# relay.net
KiCad netlist of a schematic drawn in Altium Designer
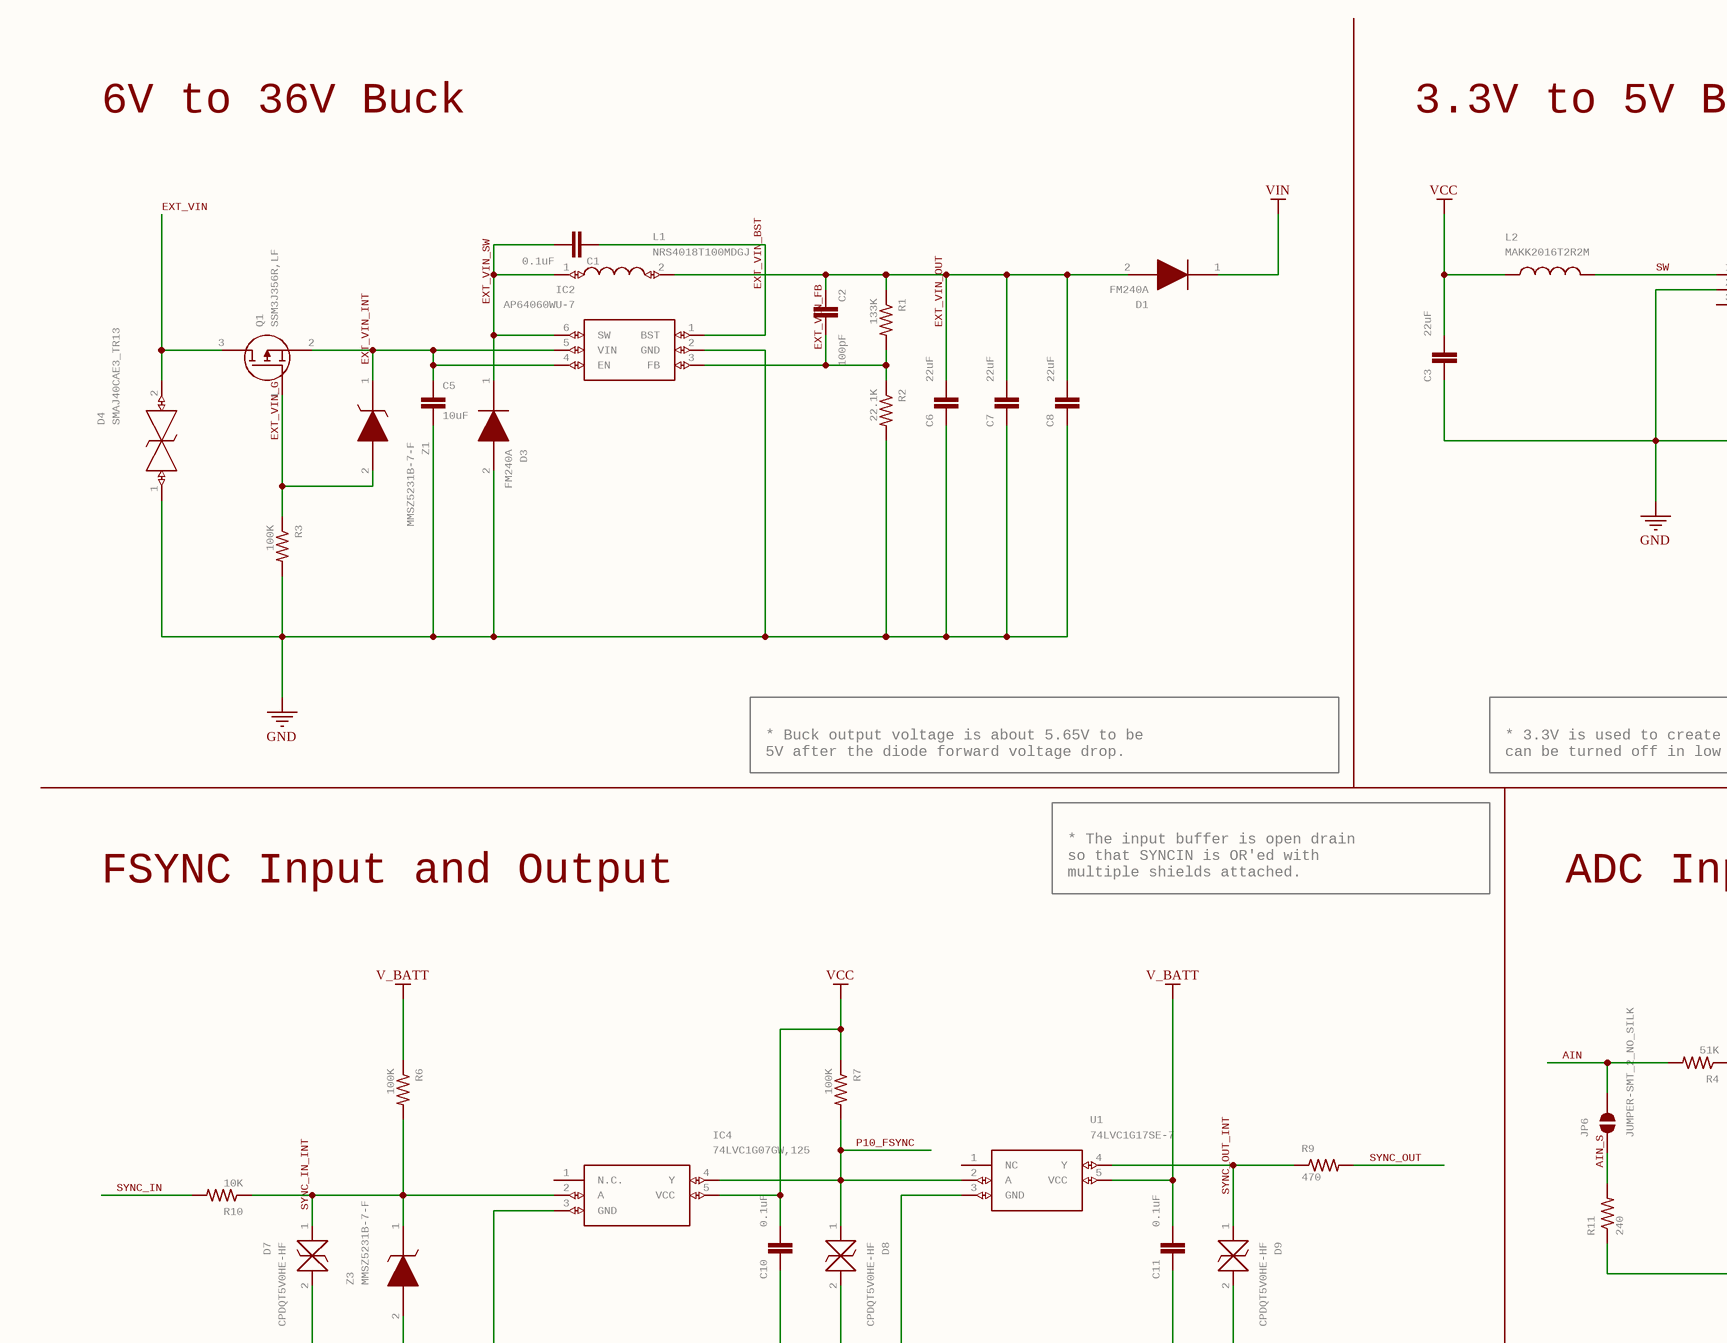
[diagram p0: relay.SchDoc, top left]
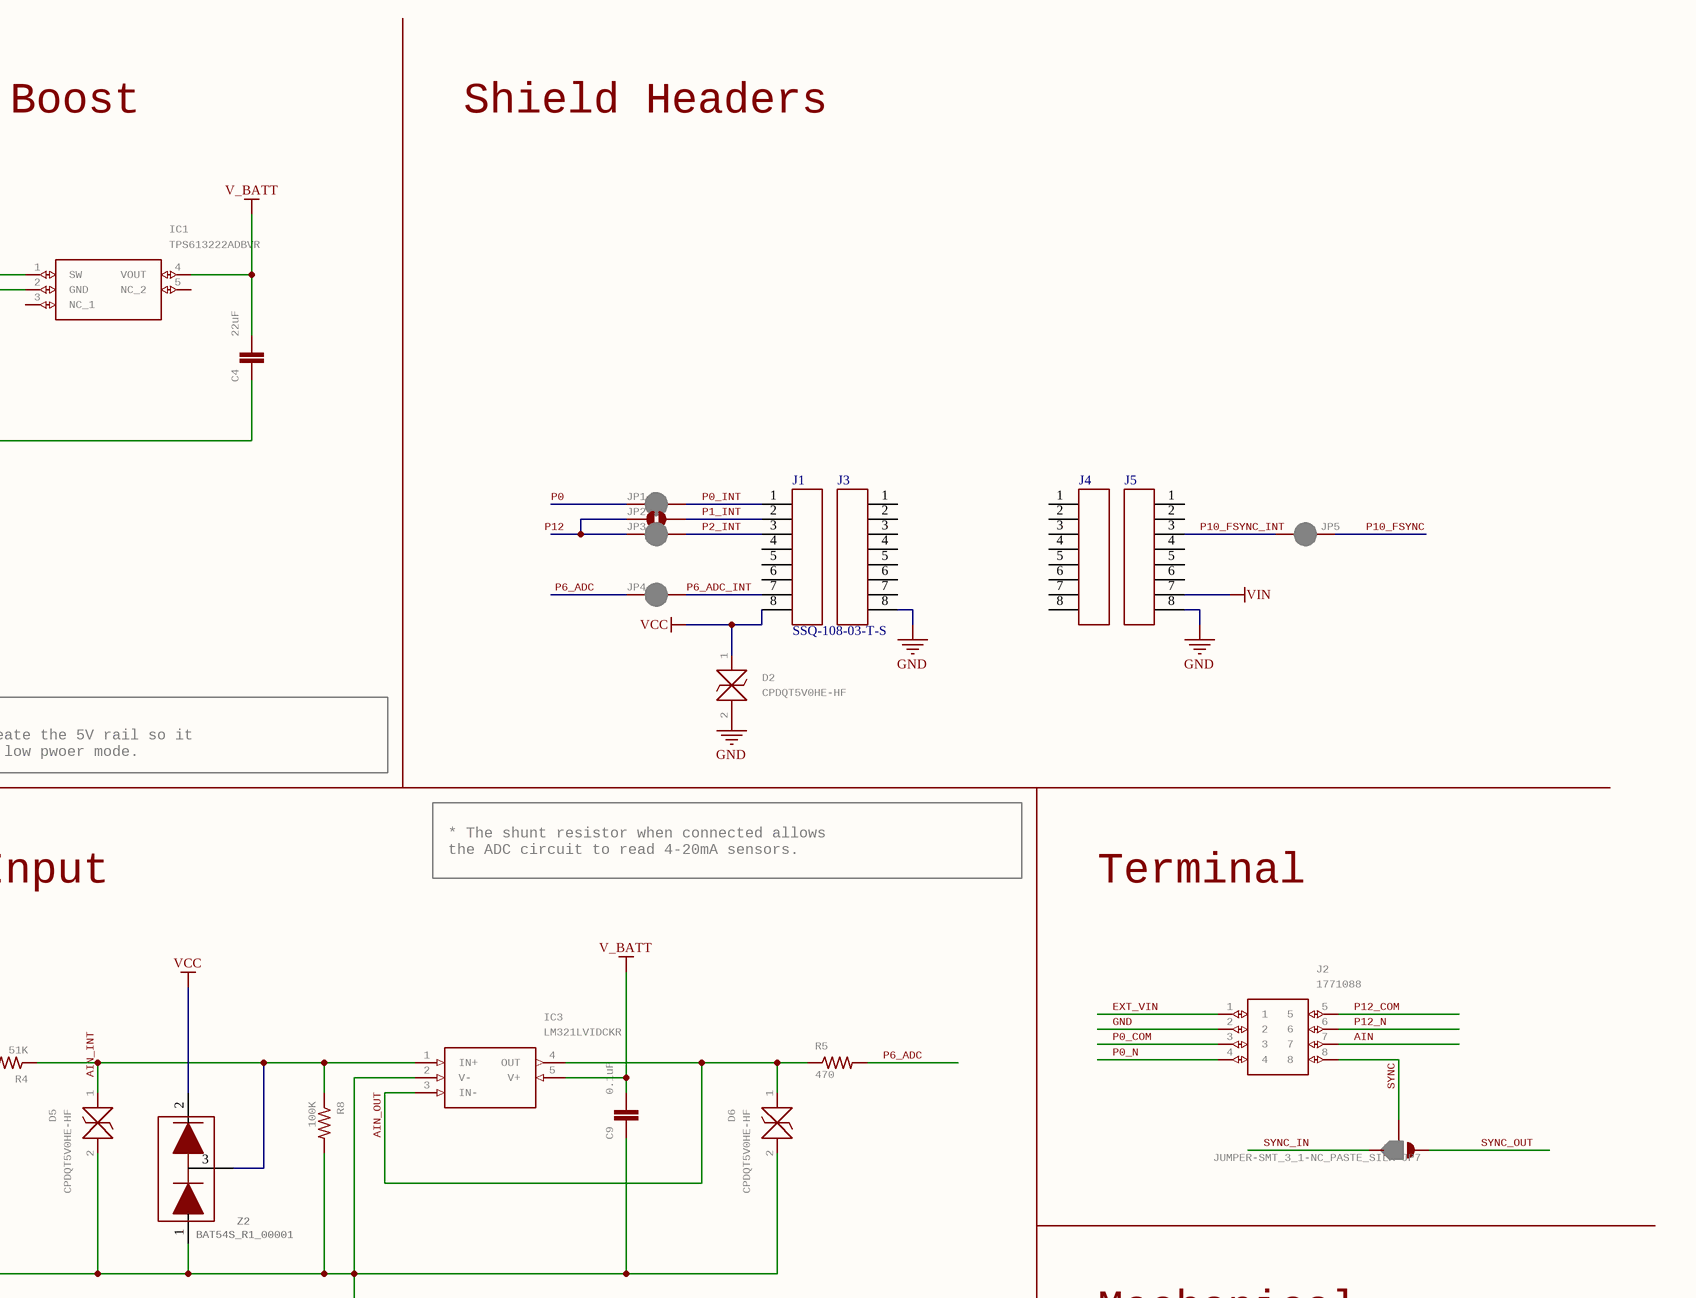
[diagram p1: relay.SchDoc, top right]
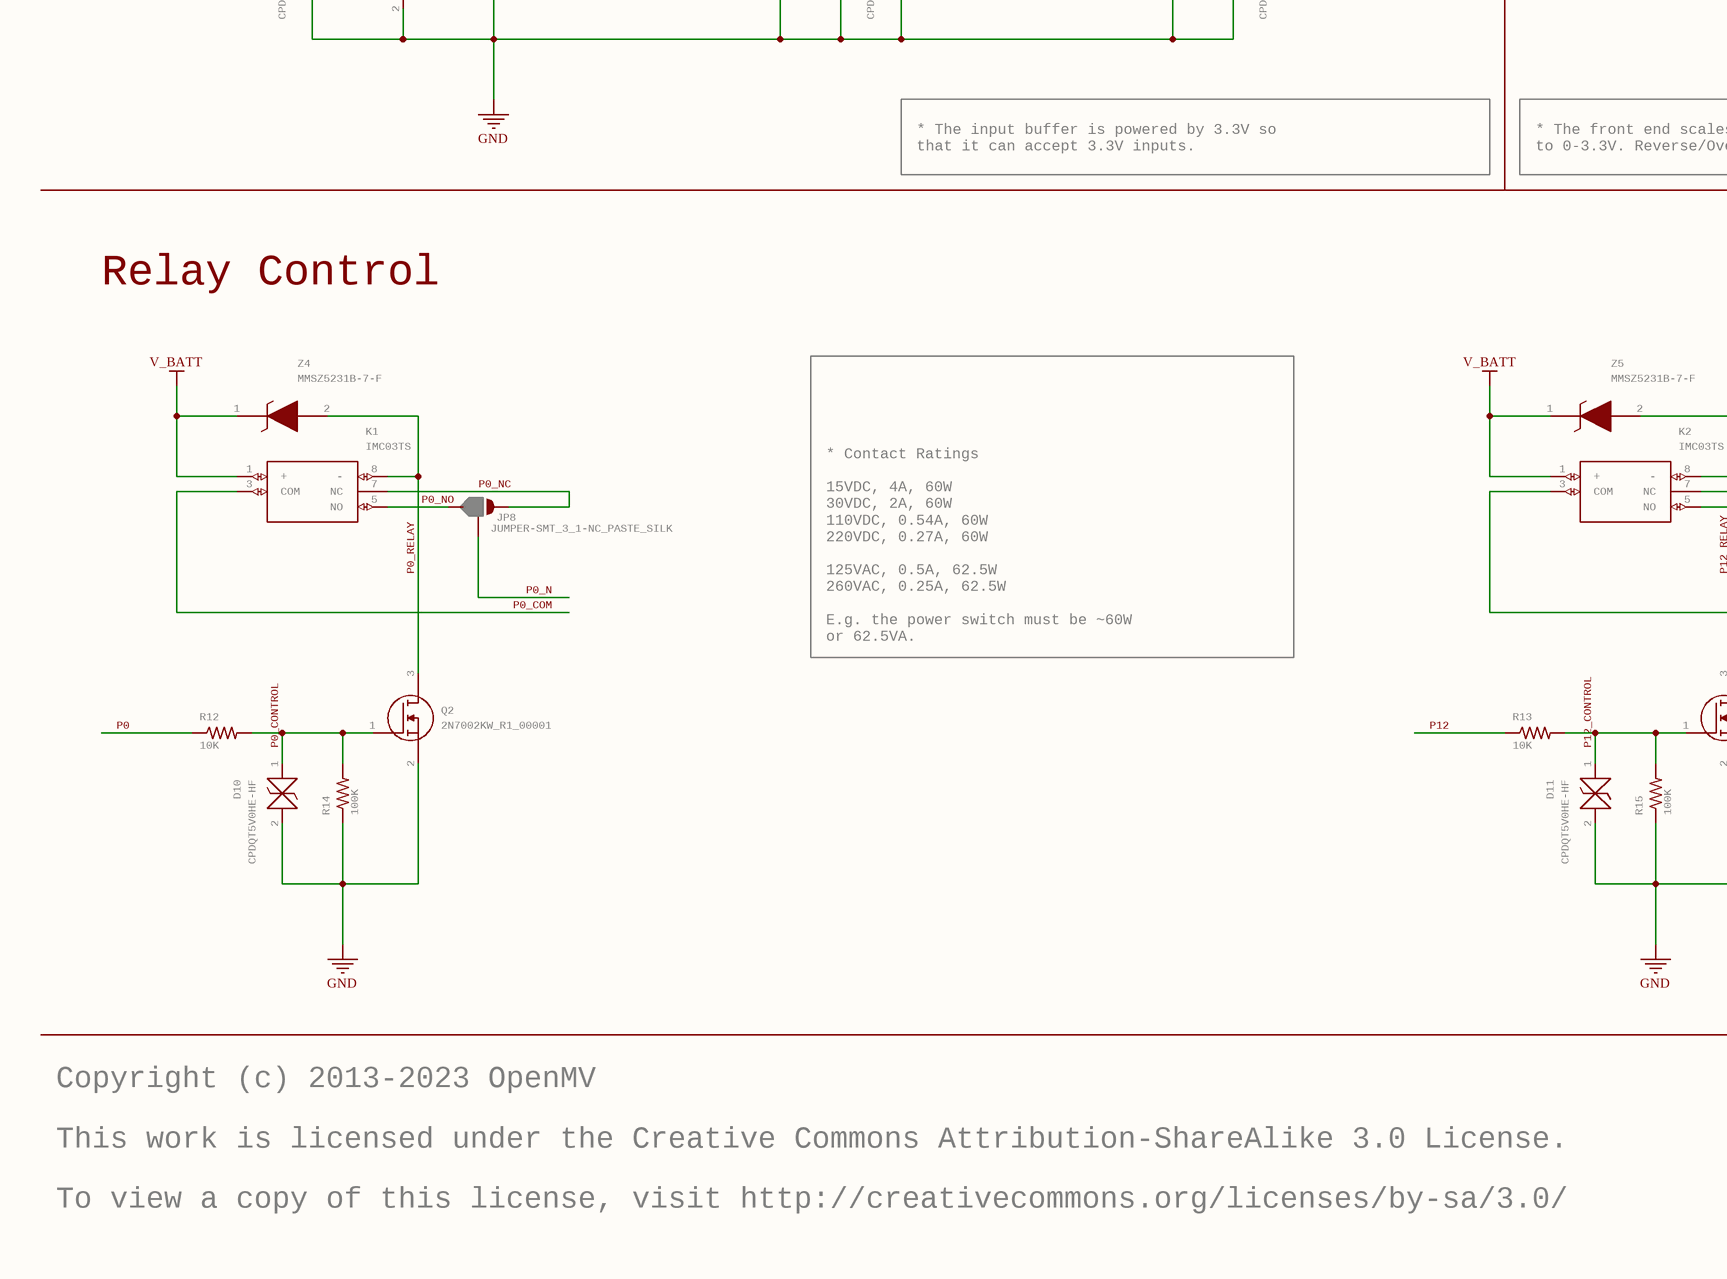
[diagram p2: relay.SchDoc, bottom left]
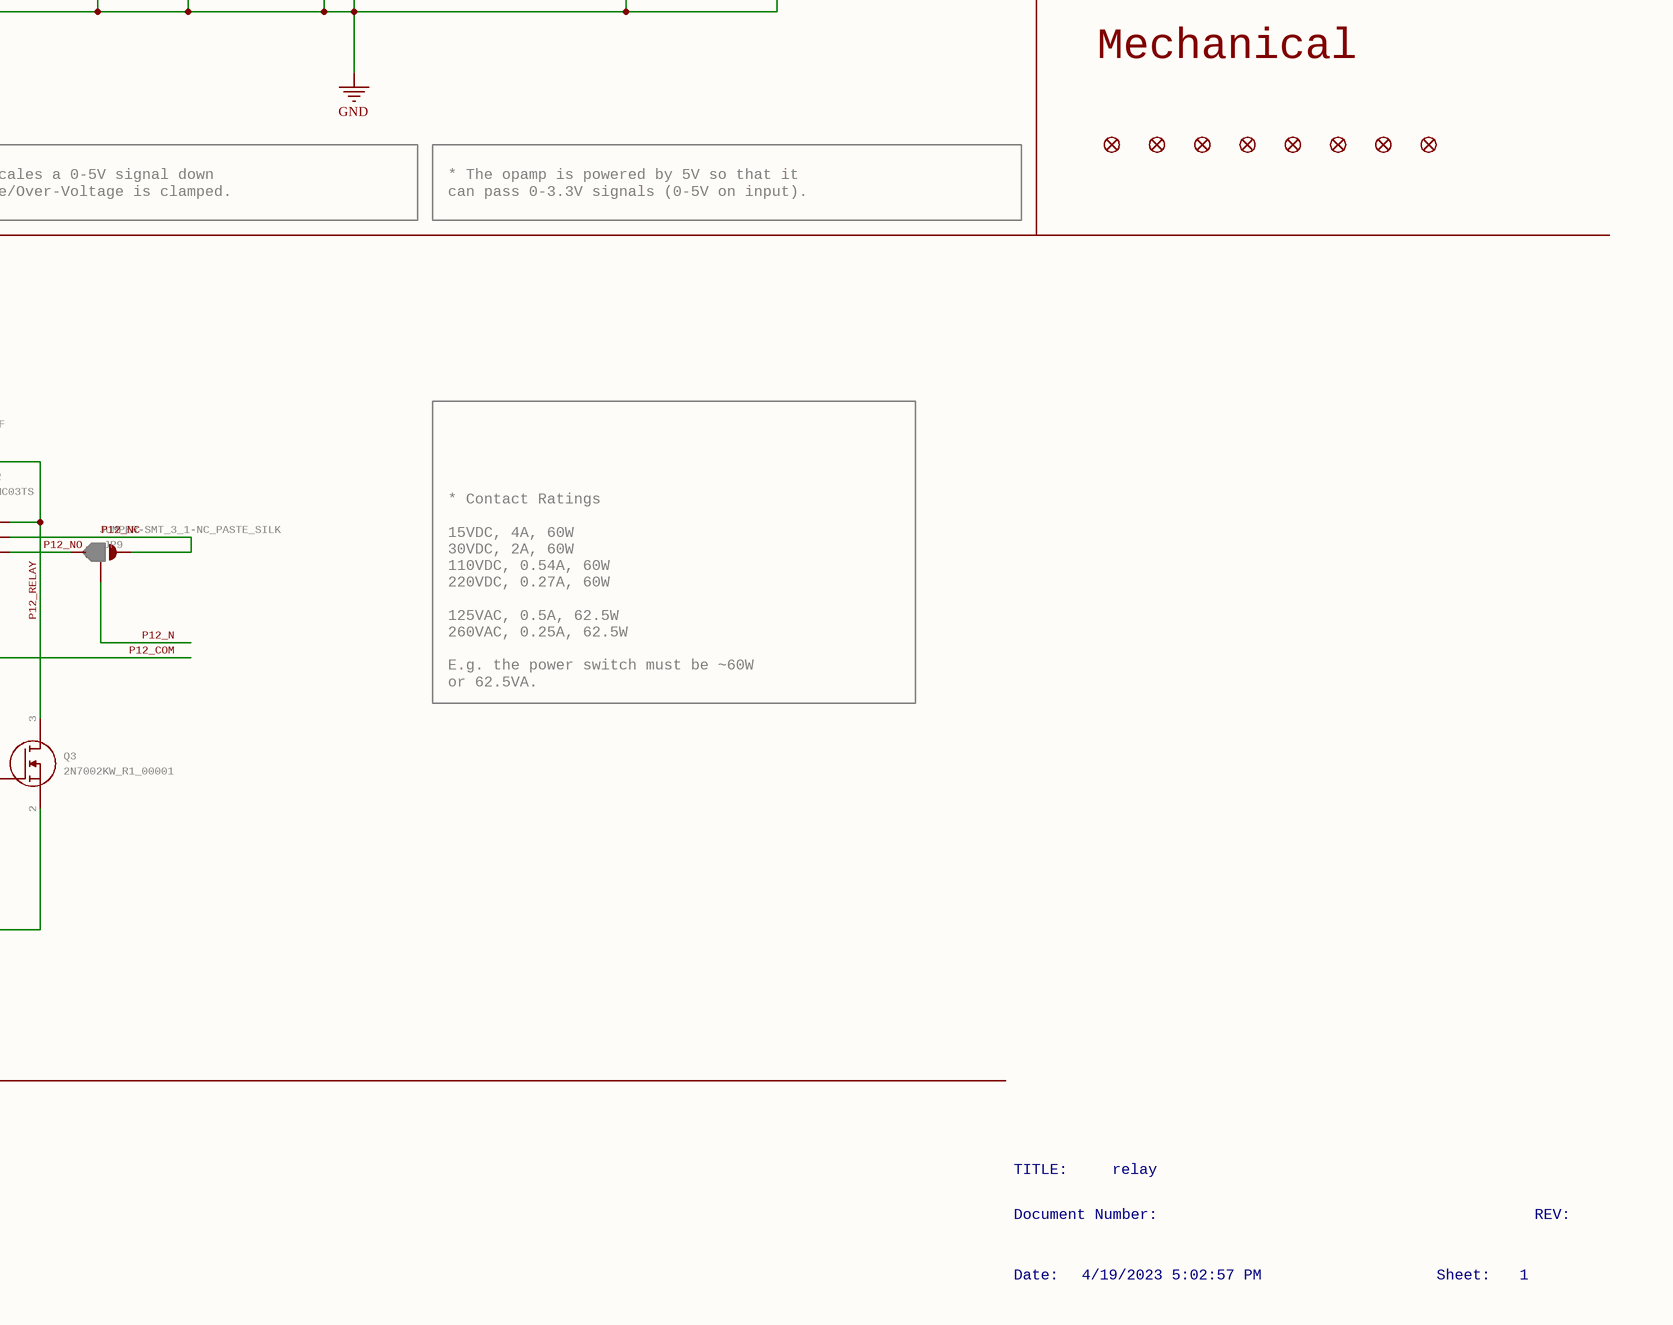
[diagram p3: relay.SchDoc, bottom right]

(export (version "E")
  (design (tool "Eeschema 10.0.6"))
  (components
    (comp (ref "C1")
      (value "0.1uF")
      (footprint "0402-CAP")
      (description "CapacitorStandard 0603 ceramic capacitor, and 0.1\" leaded capacitor.")
      (fields (field (name "MPN") "GRM155R71H104KE14D"))
      (libsource (lib "sfe") (part "CAP0402-CAP"))
    )
    (comp (ref "C2")
      (value "100pF")
      (footprint "0402-CAP")
      (description "CapacitorStandard 0603 ceramic capacitor, and 0.1\" leaded capacitor.")
      (fields (field (name "MPN") "CC0402JRNPO9BN101"))
      (libsource (lib "") (part "CAP0402-CAP_1"))
    )
    (comp (ref "C3")
      (value "22uF")
      (footprint "0805")
      (fields (field (name "MPN") "CL21A226MQQNNNE"))
      (libsource (lib "SparkFun-Capacitors") (part "22UF-0805-6.3V-20%"))
    )
    (comp (ref "C4")
      (value "22uF")
      (footprint "0805")
      (fields (field (name "MPN") "CL21A226MQQNNNE"))
      (libsource (lib "SparkFun-Capacitors") (part "22UF-0805-6.3V-20%"))
    )
    (comp (ref "C5")
      (value "10uF")
      (footprint "C0805")
      (description "CAPACITOR, European symbol")
      (fields (field (name "MPN") "GRM21BR61H106KE43K"))
      (libsource (lib "rcl") (part "C-EUC0805"))
    )
    (comp (ref "C6")
      (value "22uF")
      (footprint "0805")
      (fields (field (name "MPN") "CL21A226MQQNNNE"))
      (libsource (lib "SparkFun-Capacitors") (part "22UF-0805-6.3V-20%"))
    )
    (comp (ref "C7")
      (value "22uF")
      (footprint "0805")
      (fields (field (name "MPN") "CL21A226MQQNNNE"))
      (libsource (lib "SparkFun-Capacitors") (part "22UF-0805-6.3V-20%"))
    )
    (comp (ref "C8")
      (value "22uF")
      (footprint "0805")
      (fields (field (name "MPN") "CL21A226MQQNNNE"))
      (libsource (lib "SparkFun-Capacitors") (part "22UF-0805-6.3V-20%"))
    )
    (comp (ref "C9")
      (value "0.1uF")
      (footprint "0402-CAP")
      (description "CapacitorStandard 0603 ceramic capacitor, and 0.1\" leaded capacitor.")
      (fields (field (name "MPN") "GRM155R71H104KE14D"))
      (libsource (lib "") (part "CAP0402-CAP_2"))
    )
    (comp (ref "C10")
      (value "0.1uF")
      (footprint "0402-CAP")
      (description "CapacitorStandard 0603 ceramic capacitor, and 0.1\" leaded capacitor.")
      (fields (field (name "MPN") "GRM155R71H104KE14D"))
      (libsource (lib "") (part "CAP0402-CAP_2"))
    )
    (comp (ref "C11")
      (value "0.1uF")
      (footprint "0402-CAP")
      (description "CapacitorStandard 0603 ceramic capacitor, and 0.1\" leaded capacitor.")
      (fields (field (name "MPN") "GRM155R71H104KE14D"))
      (libsource (lib "") (part "CAP0402-CAP_2"))
    )
    (comp (ref "D1")
      (value "FM240A")
      (footprint "DIOM5025X231N")
      (description "Diodes - General Purpose, Power, Switching GP Si Rectifier SMB,2A,40V   Source:  Datasheet")
      (fields (field (name "MOUSER_PART_NUMBER") "583-FM240A"))
      (libsource (lib "FM240A") (part "FM240A"))
    )
    (comp (ref "D2")
      (value "CPDQT5V0HE-HF")
      (footprint "CPDQT5V0HEHF")
      (description "ESD Suppressors / TVS Diodes DIODE ESD 5VWM 65W 0402/SOD-923F   Source:  Datasheet")
      (fields (field (name "MOUSER_PART_NUMBER") "MOUSER_PART_NUMBER"))
      (libsource (lib "CPDQT5V0HE-HF") (part "CPDQT5V0HE-HF"))
    )
    (comp (ref "D3")
      (value "FM240A")
      (footprint "DIOM5025X231N")
      (description "Diodes - General Purpose, Power, Switching GP Si Rectifier SMB,2A,40V   Source:  Datasheet")
      (fields (field (name "MOUSER_PART_NUMBER") "583-FM240A"))
      (libsource (lib "FM240A") (part "FM240A"))
    )
    (comp (ref "D4")
      (value "SMAJ40CAE3_TR13")
      (footprint "SMAJ40CAE3TR13")
      (description "ESD Suppressors / TVS Diodes TVS   Source:  Datasheet")
      (fields
        (field (name "MANUFACTURER_PART_NUMBER") "SMAJ40CAe3/TR13")
        (field (name "MOUSER_PART_NUMBER") "494-SMAJ40CAE3/TR13")
      )
      (libsource (lib "SMAJ40CAe3_TR13") (part "SMAJ40CAE3_TR13"))
    )
    (comp (ref "D5")
      (value "CPDQT5V0HE-HF")
      (footprint "CPDQT5V0HEHF")
      (description "ESD Suppressors / TVS Diodes DIODE ESD 5VWM 65W 0402/SOD-923F   Source:  Datasheet")
      (fields (field (name "MOUSER_PART_NUMBER") "MOUSER_PART_NUMBER"))
      (libsource (lib "CPDQT5V0HE-HF") (part "CPDQT5V0HE-HF"))
    )
    (comp (ref "D6")
      (value "CPDQT5V0HE-HF")
      (footprint "CPDQT5V0HEHF")
      (description "ESD Suppressors / TVS Diodes DIODE ESD 5VWM 65W 0402/SOD-923F   Source:  Datasheet")
      (fields (field (name "MOUSER_PART_NUMBER") "MOUSER_PART_NUMBER"))
      (libsource (lib "CPDQT5V0HE-HF") (part "CPDQT5V0HE-HF"))
    )
    (comp (ref "D7")
      (value "CPDQT5V0HE-HF")
      (footprint "CPDQT5V0HEHF")
      (description "ESD Suppressors / TVS Diodes DIODE ESD 5VWM 65W 0402/SOD-923F   Source:  Datasheet")
      (fields (field (name "MOUSER_PART_NUMBER") "MOUSER_PART_NUMBER"))
      (libsource (lib "CPDQT5V0HE-HF") (part "CPDQT5V0HE-HF"))
    )
    (comp (ref "D8")
      (value "CPDQT5V0HE-HF")
      (footprint "CPDQT5V0HEHF")
      (description "ESD Suppressors / TVS Diodes DIODE ESD 5VWM 65W 0402/SOD-923F   Source:  Datasheet")
      (fields (field (name "MOUSER_PART_NUMBER") "MOUSER_PART_NUMBER"))
      (libsource (lib "CPDQT5V0HE-HF") (part "CPDQT5V0HE-HF"))
    )
    (comp (ref "D9")
      (value "CPDQT5V0HE-HF")
      (footprint "CPDQT5V0HEHF")
      (description "ESD Suppressors / TVS Diodes DIODE ESD 5VWM 65W 0402/SOD-923F   Source:  Datasheet")
      (fields (field (name "MOUSER_PART_NUMBER") "MOUSER_PART_NUMBER"))
      (libsource (lib "CPDQT5V0HE-HF") (part "CPDQT5V0HE-HF"))
    )
    (comp (ref "D10")
      (value "CPDQT5V0HE-HF")
      (footprint "CPDQT5V0HEHF")
      (description "ESD Suppressors / TVS Diodes DIODE ESD 5VWM 65W 0402/SOD-923F   Source:  Datasheet")
      (fields (field (name "MOUSER_PART_NUMBER") "MOUSER_PART_NUMBER"))
      (libsource (lib "CPDQT5V0HE-HF") (part "CPDQT5V0HE-HF"))
    )
    (comp (ref "D11")
      (value "CPDQT5V0HE-HF")
      (footprint "CPDQT5V0HEHF")
      (description "ESD Suppressors / TVS Diodes DIODE ESD 5VWM 65W 0402/SOD-923F   Source:  Datasheet")
      (fields (field (name "MOUSER_PART_NUMBER") "MOUSER_PART_NUMBER"))
      (libsource (lib "CPDQT5V0HE-HF") (part "CPDQT5V0HE-HF"))
    )
    (comp (ref "FD1")
      (value "FIDUCIAL1X2")
      (footprint "FIDUCIAL-1X2")
      (fields (field (name "LIBRARYNAME") "SparkFun-Aesthetics"))
      (libsource (lib "SparkFun-Aesthetics") (part "FIDUCIAL1X2"))
    )
    (comp (ref "FD2")
      (value "FIDUCIAL1X2")
      (footprint "FIDUCIAL-1X2")
      (fields (field (name "LIBRARYNAME") "SparkFun-Aesthetics"))
      (libsource (lib "SparkFun-Aesthetics") (part "FIDUCIAL1X2"))
    )
    (comp (ref "FD3")
      (value "FIDUCIAL1X2")
      (footprint "FIDUCIAL-1X2")
      (fields (field (name "LIBRARYNAME") "SparkFun-Aesthetics"))
      (libsource (lib "SparkFun-Aesthetics") (part "FIDUCIAL1X2"))
    )
    (comp (ref "FD4")
      (value "FIDUCIAL1X2")
      (footprint "FIDUCIAL-1X2")
      (fields (field (name "LIBRARYNAME") "SparkFun-Aesthetics"))
      (libsource (lib "SparkFun-Aesthetics") (part "FIDUCIAL1X2"))
    )
    (comp (ref "FD5")
      (value "FIDUCIAL1X2")
      (footprint "FIDUCIAL-1X2")
      (fields (field (name "LIBRARYNAME") "SparkFun-Aesthetics"))
      (libsource (lib "SparkFun-Aesthetics") (part "FIDUCIAL1X2"))
    )
    (comp (ref "FD6")
      (value "FIDUCIAL1X2")
      (footprint "FIDUCIAL-1X2")
      (fields (field (name "LIBRARYNAME") "SparkFun-Aesthetics"))
      (libsource (lib "SparkFun-Aesthetics") (part "FIDUCIAL1X2"))
    )
    (comp (ref "FD7")
      (value "FIDUCIAL1X2")
      (footprint "FIDUCIAL-1X2")
      (fields (field (name "LIBRARYNAME") "SparkFun-Aesthetics"))
      (libsource (lib "SparkFun-Aesthetics") (part "FIDUCIAL1X2"))
    )
    (comp (ref "FD8")
      (value "FIDUCIAL1X2")
      (footprint "FIDUCIAL-1X2")
      (fields (field (name "LIBRARYNAME") "SparkFun-Aesthetics"))
      (libsource (lib "SparkFun-Aesthetics") (part "FIDUCIAL1X2"))
    )
    (comp (ref "IC1")
      (value "TPS613222ADBVR")
      (footprint "SOT95P280X145-5N")
      (description "6-uA Quiescent Current, 1.8-A Switch Current Boost Converter   Source:  Datasheet")
      (fields (field (name "MOUSER_PART_NUMBER") "595-TPS613222ADBVR"))
      (libsource (lib "TPS613222ADBVR") (part "TPS613222ADBVR"))
    )
    (comp (ref "IC2")
      (value "AP64060WU-7")
      (footprint "SOT95P280X100-6N")
      (description "Switching Voltage Regulators DCDC Conv HV Buck TSOT26(STD) T&R 3K   Source:  Datasheet")
      (fields (field (name "MOUSER_PART_NUMBER") "621-AP64060WU-7"))
      (libsource (lib "AP64060WU-7") (part "AP64060WU-7"))
    )
    (comp (ref "IC3")
      (value "LM321LVIDCKR")
      (footprint "SOT65P210X110-5N")
      (description "1-Channel industry standard low voltage operational amplifier   Source:  Datasheet")
      (fields (field (name "MOUSER_PART_NUMBER") "595-LM321LVIDCKR"))
      (libsource (lib "LM321LVIDCKR") (part "LM321LVIDCKR"))
    )
    (comp (ref "IC4")
      (value "74LVC1G07GW,125")
      (footprint "SOT65P212X110-5N")
      (description "74LVC1G07 - Buffer with open-drain output@en-us   Source:  Datasheet")
      (fields (field (name "MOUSER_PART_NUMBER") "771-74LVC1G07GW-G"))
      (libsource (lib "74LVC1G07GW_125") (part "74LVC1G07GW,125"))
    )
    (comp (ref "J1") (value "SSQ-108-03-T-S") (footprint "HDR_1X8") (libsource (lib "pir") (part "HDR_1X8")))
    (comp (ref "J2")
      (value "1771088")
      (footprint "1771088")
      (fields (field (name "MOUSER_PART_NUMBER") "651-1771088"))
      (libsource (lib "1771088") (part "1771088"))
    )
    (comp (ref "J3") (value "SSQ-108-03-T-S") (footprint "HDR_1X8") (libsource (lib "") (part "HDR_1X8_1")))
    (comp (ref "J4") (value "SSQ-108-03-T-S") (footprint "HDR_1X8") (libsource (lib "pir") (part "HDR_1X8")))
    (comp (ref "J5") (value "SSQ-108-03-T-S") (footprint "HDR_1X8") (libsource (lib "") (part "HDR_1X8_1")))
    (comp (ref "JP1")
      (value "JUMPER-SMT_2_NC_PASTE_SILK")
      (footprint "SMT-JUMPER_2_NC_PASTE_SILK")
      (libsource (lib "SparkFun-Jumpers") (part "JUMPER-SMT_2_NC_PASTE_SILK"))
    )
    (comp (ref "JP2")
      (value "JUMPER-SMT_2_NO_SILK")
      (footprint "SMT-JUMPER_2_NO_SILK")
      (libsource (lib "SparkFun-Jumpers") (part "JUMPER-SMT_2_NO_SILK"))
    )
    (comp (ref "JP3")
      (value "JUMPER-SMT_2_NC_PASTE_SILK")
      (footprint "SMT-JUMPER_2_NC_PASTE_SILK")
      (libsource (lib "SparkFun-Jumpers") (part "JUMPER-SMT_2_NC_PASTE_SILK"))
    )
    (comp (ref "JP4")
      (value "JUMPER-SMT_2_NC_PASTE_SILK")
      (footprint "SMT-JUMPER_2_NC_PASTE_SILK")
      (libsource (lib "SparkFun-Jumpers") (part "JUMPER-SMT_2_NC_PASTE_SILK"))
    )
    (comp (ref "JP5")
      (value "JUMPER-SMT_2_NC_PASTE_SILK")
      (footprint "SMT-JUMPER_2_NC_PASTE_SILK")
      (libsource (lib "SparkFun-Jumpers") (part "JUMPER-SMT_2_NC_PASTE_SILK"))
    )
    (comp (ref "JP6")
      (value "JUMPER-SMT_2_NO_SILK")
      (footprint "SMT-JUMPER_2_NO_SILK")
      (libsource (lib "SparkFun-Jumpers") (part "JUMPER-SMT_2_NO_SILK"))
    )
    (comp (ref "JP7")
      (value "JUMPER-SMT_3_1-NC_PASTE_SILK")
      (footprint "SMT-JUMPER_3_1-NC_PASTE_SILK")
      (libsource (lib "") (part "JUMPER-SMT_3_1-NC_PASTE_SILK_1"))
    )
    (comp (ref "JP8")
      (value "JUMPER-SMT_3_1-NC_PASTE_SILK")
      (footprint "SMT-JUMPER_3_1-NC_PASTE_SILK")
      (libsource (lib "SparkFun-Jumpers") (part "JUMPER-SMT_3_1-NC_PASTE_SILK"))
    )
    (comp (ref "JP9")
      (value "JUMPER-SMT_3_1-NC_PASTE_SILK")
      (footprint "SMT-JUMPER_3_1-NC_PASTE_SILK")
      (libsource (lib "SparkFun-Jumpers") (part "JUMPER-SMT_3_1-NC_PASTE_SILK"))
    )
    (comp (ref "K1")
      (value "IMC03TS")
      (footprint "IMC03TS")
      (description "TE CONNECTIVITY - IMC03TS - RELAY, SIGNAL, SPDT, 30VDC, 2A   Source:  Datasheet")
      (fields (field (name "MOUSER_PART_NUMBER") "655-IMC03TS") (field (name "MPN") "IMC03CTS"))
      (libsource (lib "IMC03TS") (part "IMC03TS"))
    )
    (comp (ref "K2")
      (value "IMC03TS")
      (footprint "IMC03TS")
      (description "TE CONNECTIVITY - IMC03TS - RELAY, SIGNAL, SPDT, 30VDC, 2A   Source:  Datasheet")
      (fields (field (name "MOUSER_PART_NUMBER") "655-IMC03TS") (field (name "MPN") "IMC03CTS"))
      (libsource (lib "IMC03TS") (part "IMC03TS"))
    )
    (comp (ref "L1")
      (value "NRS4018T100MDGJ")
      (footprint "NRS4018T100MDGJ")
      (description "Fixed Inductors 4018 10uH 180mOhms +/-20%Tol 1200mA   Source:  Datasheet")
      (fields (field (name "MOUSER_PART_NUMBER") "963-NRS4018T100MDGJ"))
      (libsource (lib "NRS4018T100MDGJ") (part "NRS4018T100MDGJ"))
    )
    (comp (ref "L2")
      (value "MAKK2016T2R2M")
      (footprint "INDC2016X100N")
      (description "INDUCTOR, METAL CORE Check availability")
      (fields (field (name "MF") "Taiyo Yuden"))
      (libsource (lib "MAKK2016T2R2M") (part "MAKK2016T2R2M"))
    )
    (comp (ref "Q1")
      (value "SSM3J356R,LF")
      (footprint "SOTFL95P240X88-3N")
      (description "MOSFET Small-signal MOSFET ID: -2A, VDSS: -60V   Source:  Datasheet")
      (fields (field (name "MOUSER_PART_NUMBER") "757-SSM3J356RLF"))
      (libsource (lib "SSM3J356R_LF") (part "SSM3J356R,LF"))
    )
    (comp (ref "Q2")
      (value "2N7002KW_R1_00001")
      (footprint "SOT65P210X110-3N")
      (description "MOSFET 60V N-Channel Enhancement Mode MOSFET - ESD Protected   Source:  Datasheet")
      (fields (field (name "MOUSER_PART_NUMBER") "241-2N7002KWR100001"))
      (libsource (lib "2N7002KW_R1_00001") (part "2N7002KW_R1_00001"))
    )
    (comp (ref "Q3")
      (value "2N7002KW_R1_00001")
      (footprint "SOT65P210X110-3N")
      (description "MOSFET 60V N-Channel Enhancement Mode MOSFET - ESD Protected   Source:  Datasheet")
      (fields (field (name "MOUSER_PART_NUMBER") "241-2N7002KWR100001"))
      (libsource (lib "2N7002KW_R1_00001") (part "2N7002KW_R1_00001"))
    )
    (comp (ref "R1")
      (value "133K")
      (footprint "0402-RES")
      (description "ResistorBasic schematic elements and footprints for 0603, 1206, and PTH resistors.")
      (fields (field (name "MPN") "RC0402FR-07133KL"))
      (libsource (lib "sfe") (part "RESISTOR0402-RES"))
    )
    (comp (ref "R2")
      (value "22.1K")
      (footprint "0402-RES")
      (description "ResistorBasic schematic elements and footprints for 0603, 1206, and PTH resistors.")
      (fields (field (name "MPN") "CR0402-FX-2212GLF"))
      (libsource (lib "sfe") (part "RESISTOR0402-RES"))
    )
    (comp (ref "R3")
      (value "100K")
      (footprint "0402-RES")
      (description "ResistorBasic schematic elements and footprints for 0603, 1206, and PTH resistors.")
      (fields (field (name "MPN") "AC0402FR-07100KL"))
      (libsource (lib "sfe") (part "RESISTOR0402-RES"))
    )
    (comp (ref "R4")
      (value "51K")
      (footprint "0402-RES")
      (description "ResistorBasic schematic elements and footprints for 0603, 1206, and PTH resistors.")
      (fields (field (name "MPN") "RC0402JR-0751KL"))
      (libsource (lib "sfe") (part "RESISTOR0402-RES"))
    )
    (comp (ref "R5")
      (value "470")
      (footprint "R0603")
      (description "RESISTOR, American symbol")
      (fields (field (name "MPN") "CR0603-FX-4700ELF"))
      (libsource (lib "rcl") (part "R-US_R0603"))
    )
    (comp (ref "R6")
      (value "100K")
      (footprint "0402-RES")
      (description "ResistorBasic schematic elements and footprints for 0603, 1206, and PTH resistors.")
      (fields (field (name "MPN") "AC0402FR-07100KL"))
      (libsource (lib "sfe") (part "RESISTOR0402-RES"))
    )
    (comp (ref "R7")
      (value "100K")
      (footprint "0402-RES")
      (description "ResistorBasic schematic elements and footprints for 0603, 1206, and PTH resistors.")
      (fields (field (name "MPN") "AC0402FR-07100KL"))
      (libsource (lib "sfe") (part "RESISTOR0402-RES"))
    )
    (comp (ref "R8")
      (value "100K")
      (footprint "0402-RES")
      (description "ResistorBasic schematic elements and footprints for 0603, 1206, and PTH resistors.")
      (fields (field (name "MPN") "AC0402FR-07100KL"))
      (libsource (lib "sfe") (part "RESISTOR0402-RES"))
    )
    (comp (ref "R9")
      (value "470")
      (footprint "R0603")
      (description "RESISTOR, American symbol")
      (fields (field (name "MPN") "CR0603-FX-4700ELF"))
      (libsource (lib "rcl") (part "R-US_R0603"))
    )
    (comp (ref "R10")
      (value "10K")
      (footprint "0402-RES")
      (description "ResistorBasic schematic elements and footprints for 0603, 1206, and PTH resistors.")
      (fields (field (name "MPN") "AC0402FR-1310KL"))
      (libsource (lib "sfe") (part "RESISTOR0402-RES"))
    )
    (comp (ref "R11")
      (value "240")
      (footprint "R0603")
      (description "RESISTOR, American symbol")
      (fields (field (name "MPN") "RK73B1JTTD241J"))
      (libsource (lib "rcl") (part "R-US_R0603"))
    )
    (comp (ref "R12")
      (value "10K")
      (footprint "0402-RES")
      (description "ResistorBasic schematic elements and footprints for 0603, 1206, and PTH resistors.")
      (fields (field (name "MPN") "AC0402FR-1310KL"))
      (libsource (lib "sfe") (part "RESISTOR0402-RES"))
    )
    (comp (ref "R13")
      (value "10K")
      (footprint "0402-RES")
      (description "ResistorBasic schematic elements and footprints for 0603, 1206, and PTH resistors.")
      (fields (field (name "MPN") "AC0402FR-1310KL"))
      (libsource (lib "sfe") (part "RESISTOR0402-RES"))
    )
    (comp (ref "R14")
      (value "100K")
      (footprint "0402-RES")
      (description "ResistorBasic schematic elements and footprints for 0603, 1206, and PTH resistors.")
      (fields (field (name "MPN") "AC0402FR-07100KL"))
      (libsource (lib "sfe") (part "RESISTOR0402-RES"))
    )
    (comp (ref "R15")
      (value "100K")
      (footprint "0402-RES")
      (description "ResistorBasic schematic elements and footprints for 0603, 1206, and PTH resistors.")
      (fields (field (name "MPN") "AC0402FR-07100KL"))
      (libsource (lib "sfe") (part "RESISTOR0402-RES"))
    )
    (comp (ref "U1")
      (value "74LVC1G17SE-7")
      (footprint "SOT65P210X110-5N")
      (fields (field (name "MOUSER_PART_NUMBER") "621-74LVC1G17SE-7"))
      (libsource (lib "74LVC1G17SE-7") (part "74LVC1G17SE-7"))
    )
    (comp (ref "Z1")
      (value "MMSZ5231B-7-F")
      (footprint "SOD3716X145N")
      (fields (field (name "MOUSER_PART_NUMBER") "621-MMSZ5231B-F"))
      (libsource (lib "MMSZ5231B-7-F") (part "MMSZ5231B-7-F"))
    )
    (comp (ref "Z2")
      (value "BAT54S_R1_00001")
      (footprint "SOT23-3")
      (libsource (lib "can-rs232") (part "BAT54S_R1_00001"))
    )
    (comp (ref "Z3")
      (value "MMSZ5231B-7-F")
      (footprint "SOD3716X145N")
      (fields (field (name "MOUSER_PART_NUMBER") "621-MMSZ5231B-F"))
      (libsource (lib "MMSZ5231B-7-F") (part "MMSZ5231B-7-F"))
    )
    (comp (ref "Z4")
      (value "MMSZ5231B-7-F")
      (footprint "SOD3716X145N")
      (fields (field (name "MOUSER_PART_NUMBER") "621-MMSZ5231B-F"))
      (libsource (lib "MMSZ5231B-7-F") (part "MMSZ5231B-7-F"))
    )
    (comp (ref "Z5")
      (value "MMSZ5231B-7-F")
      (footprint "SOD3716X145N")
      (fields (field (name "MOUSER_PART_NUMBER") "621-MMSZ5231B-F"))
      (libsource (lib "MMSZ5231B-7-F") (part "MMSZ5231B-7-F"))
    )
  )
  (nets
    (net (code "1") (name "/AIN") (class "Default")
      (node (ref "J2") (pin "7") (pinfunction "7_7") (pintype "bidirectional"))
      (node (ref "JP6") (pin "2") (pinfunction "2_2") (pintype "passive"))
      (node (ref "R4") (pin "2") (pinfunction "2_2") (pintype "passive"))
    )
    (net (code "2") (name "/AIN_INT") (class "Default")
      (node (ref "D5") (pin "1") (pinfunction "1_1") (pintype "bidirectional"))
      (node (ref "IC3") (pin "1") (pinfunction "IN+_1") (pintype "input"))
      (node (ref "R4") (pin "1") (pinfunction "1_1") (pintype "passive"))
      (node (ref "R8") (pin "1") (pinfunction "1_1") (pintype "passive"))
      (node (ref "Z2") (pin "3") (pintype "passive"))
    )
    (net (code "3") (name "/AIN_OUT") (class "Default")
      (node (ref "D6") (pin "1") (pinfunction "1_1") (pintype "bidirectional"))
      (node (ref "IC3") (pin "3") (pinfunction "IN-_3") (pintype "input"))
      (node (ref "IC3") (pin "4") (pinfunction "OUT_4") (pintype "output"))
      (node (ref "R5") (pin "1") (pinfunction "1_1") (pintype "passive"))
    )
    (net (code "4") (name "/AIN_S") (class "Default")
      (node (ref "JP6") (pin "1") (pinfunction "1_1") (pintype "passive"))
      (node (ref "R11") (pin "2") (pinfunction "2_2") (pintype "passive"))
    )
    (net (code "5") (name "/EXT_VIN") (class "Default")
      (node (ref "D4") (pin "2") (pinfunction "2_2") (pintype "bidirectional"))
      (node (ref "J2") (pin "1") (pinfunction "1_1") (pintype "bidirectional"))
      (node (ref "Q1") (pin "3") (pinfunction "D_3") (pintype "bidirectional"))
    )
    (net (code "6") (name "/EXT_VIN_BST") (class "Default")
      (node (ref "C1") (pin "1") (pinfunction "1_1") (pintype "passive"))
      (node (ref "IC2") (pin "1") (pinfunction "BST_1") (pintype "bidirectional"))
    )
    (net (code "7") (name "/EXT_VIN_FB") (class "Default")
      (node (ref "C2") (pin "2") (pinfunction "2_2") (pintype "passive"))
      (node (ref "IC2") (pin "3") (pinfunction "FB_3") (pintype "bidirectional"))
      (node (ref "R1") (pin "2") (pinfunction "2_2") (pintype "passive"))
      (node (ref "R2") (pin "1") (pinfunction "1_1") (pintype "passive"))
    )
    (net (code "8") (name "/EXT_VIN_G") (class "Default")
      (node (ref "Q1") (pin "1") (pinfunction "G_1") (pintype "bidirectional"))
      (node (ref "R3") (pin "1") (pinfunction "1_1") (pintype "passive"))
      (node (ref "Z1") (pin "2") (pinfunction "A_2") (pintype "bidirectional"))
    )
    (net (code "9") (name "/EXT_VIN_INT") (class "Default")
      (node (ref "C5") (pin "1") (pinfunction "1_1") (pintype "passive"))
      (node (ref "IC2") (pin "4") (pinfunction "EN_4") (pintype "bidirectional"))
      (node (ref "IC2") (pin "5") (pinfunction "VIN_5") (pintype "bidirectional"))
      (node (ref "Q1") (pin "2") (pinfunction "S_2") (pintype "bidirectional"))
      (node (ref "Z1") (pin "1") (pinfunction "K_1") (pintype "bidirectional"))
    )
    (net (code "10") (name "/EXT_VIN_OUT") (class "Default")
      (node (ref "C2") (pin "1") (pinfunction "1_1") (pintype "passive"))
      (node (ref "C6") (pin "2") (pinfunction "2_2") (pintype "passive"))
      (node (ref "C7") (pin "2") (pinfunction "2_2") (pintype "passive"))
      (node (ref "C8") (pin "2") (pinfunction "2_2") (pintype "passive"))
      (node (ref "D1") (pin "2") (pinfunction "A_2") (pintype "bidirectional"))
      (node (ref "L1") (pin "2") (pinfunction "2_2") (pintype "bidirectional"))
      (node (ref "R1") (pin "1") (pinfunction "1_1") (pintype "passive"))
    )
    (net (code "11") (name "/EXT_VIN_SW") (class "Default")
      (node (ref "C1") (pin "2") (pinfunction "2_2") (pintype "passive"))
      (node (ref "D3") (pin "1") (pinfunction "K_1") (pintype "bidirectional"))
      (node (ref "IC2") (pin "6") (pinfunction "SW_6") (pintype "bidirectional"))
      (node (ref "L1") (pin "1") (pinfunction "1_1") (pintype "bidirectional"))
    )
    (net (code "12") (name "/P0") (class "Default")
      (node (ref "JP1") (pin "2") (pinfunction "2_2") (pintype "passive"))
      (node (ref "R12") (pin "1") (pinfunction "1_1") (pintype "passive"))
    )
    (net (code "13") (name "/P0_COM") (class "Default")
      (node (ref "J2") (pin "3") (pinfunction "3_3") (pintype "bidirectional"))
      (node (ref "K1") (pin "3") (pinfunction "COM_3") (pintype "bidirectional"))
    )
    (net (code "14") (name "/P0_CONTROL") (class "Default")
      (node (ref "D10") (pin "1") (pinfunction "1_1") (pintype "bidirectional"))
      (node (ref "Q2") (pin "1") (pinfunction "G_1") (pintype "bidirectional"))
      (node (ref "R12") (pin "2") (pinfunction "2_2") (pintype "passive"))
      (node (ref "R14") (pin "2") (pinfunction "2_2") (pintype "passive"))
    )
    (net (code "15") (name "/P0_INT") (class "Default")
      (node (ref "J1") (pin "1") (pintype "passive"))
      (node (ref "JP1") (pin "1") (pinfunction "1_1") (pintype "passive"))
    )
    (net (code "16") (name "/P0_N") (class "Default")
      (node (ref "J2") (pin "4") (pinfunction "4_4") (pintype "bidirectional"))
      (node (ref "JP8") (pin "2") (pinfunction "2_2") (pintype "passive"))
    )
    (net (code "17") (name "/P0_NC") (class "Default")
      (node (ref "JP8") (pin "1") (pinfunction "1_1") (pintype "passive"))
      (node (ref "K1") (pin "7") (pinfunction "NC_7") (pintype "passive"))
    )
    (net (code "18") (name "/P0_NO") (class "Default")
      (node (ref "JP8") (pin "3") (pinfunction "3_3") (pintype "passive"))
      (node (ref "K1") (pin "5") (pinfunction "NO_5") (pintype "bidirectional"))
    )
    (net (code "19") (name "/P0_RELAY") (class "Default")
      (node (ref "K1") (pin "8") (pinfunction "-_8") (pintype "bidirectional"))
      (node (ref "Q2") (pin "3") (pinfunction "D_3") (pintype "bidirectional"))
      (node (ref "Z4") (pin "2") (pinfunction "A_2") (pintype "bidirectional"))
    )
    (net (code "20") (name "/P1_INT") (class "Default")
      (node (ref "J1") (pin "2") (pintype "passive"))
      (node (ref "JP2") (pin "1") (pinfunction "1_1") (pintype "passive"))
    )
    (net (code "21") (name "/P2_INT") (class "Default")
      (node (ref "J1") (pin "3") (pintype "passive"))
      (node (ref "JP3") (pin "1") (pinfunction "1_1") (pintype "passive"))
    )
    (net (code "22") (name "/P6_ADC") (class "Default")
      (node (ref "JP4") (pin "2") (pinfunction "2_2") (pintype "passive"))
      (node (ref "R5") (pin "2") (pinfunction "2_2") (pintype "passive"))
    )
    (net (code "23") (name "/P6_ADC_INT") (class "Default")
      (node (ref "J1") (pin "7") (pintype "passive"))
      (node (ref "JP4") (pin "1") (pinfunction "1_1") (pintype "passive"))
    )
    (net (code "24") (name "/P10_FSYNC") (class "Default")
      (node (ref "D8") (pin "1") (pinfunction "1_1") (pintype "bidirectional"))
      (node (ref "IC4") (pin "4") (pinfunction "Y_4") (pintype "bidirectional"))
      (node (ref "JP5") (pin "2") (pinfunction "2_2") (pintype "passive"))
      (node (ref "R7") (pin "2") (pinfunction "2_2") (pintype "passive"))
      (node (ref "U1") (pin "2") (pinfunction "A_2") (pintype "bidirectional"))
    )
    (net (code "25") (name "/P10_FSYNC_INT") (class "Default")
      (node (ref "J5") (pin "3") (pintype "passive"))
      (node (ref "JP5") (pin "1") (pinfunction "1_1") (pintype "passive"))
    )
    (net (code "26") (name "/P12") (class "Default")
      (node (ref "JP2") (pin "2") (pinfunction "2_2") (pintype "passive"))
      (node (ref "JP3") (pin "2") (pinfunction "2_2") (pintype "passive"))
      (node (ref "R13") (pin "1") (pinfunction "1_1") (pintype "passive"))
    )
    (net (code "27") (name "/P12_COM") (class "Default")
      (node (ref "J2") (pin "5") (pinfunction "5_5") (pintype "bidirectional"))
      (node (ref "K2") (pin "3") (pinfunction "COM_3") (pintype "bidirectional"))
    )
    (net (code "28") (name "/P12_CONTROL") (class "Default")
      (node (ref "D11") (pin "1") (pinfunction "1_1") (pintype "bidirectional"))
      (node (ref "Q3") (pin "1") (pinfunction "G_1") (pintype "bidirectional"))
      (node (ref "R13") (pin "2") (pinfunction "2_2") (pintype "passive"))
      (node (ref "R15") (pin "2") (pinfunction "2_2") (pintype "passive"))
    )
    (net (code "29") (name "/P12_N") (class "Default")
      (node (ref "J2") (pin "6") (pinfunction "6_6") (pintype "bidirectional"))
      (node (ref "JP9") (pin "2") (pinfunction "2_2") (pintype "passive"))
    )
    (net (code "30") (name "/P12_NC") (class "Default")
      (node (ref "JP9") (pin "1") (pinfunction "1_1") (pintype "passive"))
      (node (ref "K2") (pin "7") (pinfunction "NC_7") (pintype "passive"))
    )
    (net (code "31") (name "/P12_NO") (class "Default")
      (node (ref "JP9") (pin "3") (pinfunction "3_3") (pintype "passive"))
      (node (ref "K2") (pin "5") (pinfunction "NO_5") (pintype "bidirectional"))
    )
    (net (code "32") (name "/P12_RELAY") (class "Default")
      (node (ref "K2") (pin "8") (pinfunction "-_8") (pintype "bidirectional"))
      (node (ref "Q3") (pin "3") (pinfunction "D_3") (pintype "bidirectional"))
      (node (ref "Z5") (pin "2") (pinfunction "A_2") (pintype "bidirectional"))
    )
    (net (code "33") (name "/SW") (class "Default")
      (node (ref "IC1") (pin "1") (pinfunction "SW_1") (pintype "bidirectional"))
      (node (ref "L2") (pin "2") (pinfunction "2_2") (pintype "passive"))
    )
    (net (code "34") (name "/SYNC") (class "Default")
      (node (ref "J2") (pin "8") (pinfunction "8_8") (pintype "bidirectional"))
      (node (ref "JP7") (pin "2") (pinfunction "2_2") (pintype "passive"))
    )
    (net (code "35") (name "/SYNC_IN") (class "Default")
      (node (ref "JP7") (pin "3") (pinfunction "3_3") (pintype "passive"))
      (node (ref "R10") (pin "2") (pinfunction "2_2") (pintype "passive"))
    )
    (net (code "36") (name "/SYNC_IN_INT") (class "Default")
      (node (ref "D7") (pin "1") (pinfunction "1_1") (pintype "bidirectional"))
      (node (ref "IC4") (pin "2") (pinfunction "A_2") (pintype "bidirectional"))
      (node (ref "R10") (pin "1") (pinfunction "1_1") (pintype "passive"))
      (node (ref "R6") (pin "2") (pinfunction "2_2") (pintype "passive"))
      (node (ref "Z3") (pin "1") (pinfunction "K_1") (pintype "bidirectional"))
    )
    (net (code "37") (name "/SYNC_OUT") (class "Default")
      (node (ref "JP7") (pin "1") (pinfunction "1_1") (pintype "passive"))
      (node (ref "R9") (pin "2") (pinfunction "2_2") (pintype "passive"))
    )
    (net (code "38") (name "/SYNC_OUT_INT") (class "Default")
      (node (ref "D9") (pin "1") (pinfunction "1_1") (pintype "bidirectional"))
      (node (ref "R9") (pin "1") (pinfunction "1_1") (pintype "passive"))
      (node (ref "U1") (pin "4") (pinfunction "Y_4") (pintype "bidirectional"))
    )
    (net (code "39") (name "GND") (class "Default")
      (node (ref "C10") (pin "1") (pinfunction "1_1") (pintype "passive"))
      (node (ref "C11") (pin "1") (pinfunction "1_1") (pintype "passive"))
      (node (ref "C3") (pin "1") (pinfunction "1_1") (pintype "passive"))
      (node (ref "C4") (pin "1") (pinfunction "1_1") (pintype "passive"))
      (node (ref "C5") (pin "2") (pinfunction "2_2") (pintype "passive"))
      (node (ref "C6") (pin "1") (pinfunction "1_1") (pintype "passive"))
      (node (ref "C7") (pin "1") (pinfunction "1_1") (pintype "passive"))
      (node (ref "C8") (pin "1") (pinfunction "1_1") (pintype "passive"))
      (node (ref "C9") (pin "1") (pinfunction "1_1") (pintype "passive"))
      (node (ref "D10") (pin "2") (pinfunction "2_2") (pintype "bidirectional"))
      (node (ref "D11") (pin "2") (pinfunction "2_2") (pintype "bidirectional"))
      (node (ref "D2") (pin "2") (pinfunction "2_2") (pintype "bidirectional"))
      (node (ref "D3") (pin "2") (pinfunction "A_2") (pintype "bidirectional"))
      (node (ref "D4") (pin "1") (pinfunction "1_1") (pintype "bidirectional"))
      (node (ref "D5") (pin "2") (pinfunction "2_2") (pintype "bidirectional"))
      (node (ref "D6") (pin "2") (pinfunction "2_2") (pintype "bidirectional"))
      (node (ref "D7") (pin "2") (pinfunction "2_2") (pintype "bidirectional"))
      (node (ref "D8") (pin "2") (pinfunction "2_2") (pintype "bidirectional"))
      (node (ref "D9") (pin "2") (pinfunction "2_2") (pintype "bidirectional"))
      (node (ref "IC1") (pin "2") (pinfunction "GND_2") (pintype "bidirectional"))
      (node (ref "IC2") (pin "2") (pinfunction "GND_2") (pintype "bidirectional"))
      (node (ref "IC3") (pin "2") (pinfunction "V-_2") (pintype "input"))
      (node (ref "IC4") (pin "3") (pinfunction "GND_3") (pintype "bidirectional"))
      (node (ref "J2") (pin "2") (pinfunction "2_2") (pintype "bidirectional"))
      (node (ref "J3") (pin "8") (pintype "passive"))
      (node (ref "J5") (pin "8") (pintype "passive"))
      (node (ref "Q2") (pin "2") (pinfunction "S_2") (pintype "bidirectional"))
      (node (ref "Q3") (pin "2") (pinfunction "S_2") (pintype "bidirectional"))
      (node (ref "R11") (pin "1") (pinfunction "1_1") (pintype "passive"))
      (node (ref "R14") (pin "1") (pinfunction "1_1") (pintype "passive"))
      (node (ref "R15") (pin "1") (pinfunction "1_1") (pintype "passive"))
      (node (ref "R2") (pin "2") (pinfunction "2_2") (pintype "passive"))
      (node (ref "R3") (pin "2") (pinfunction "2_2") (pintype "passive"))
      (node (ref "R8") (pin "2") (pinfunction "2_2") (pintype "passive"))
      (node (ref "U1") (pin "3") (pinfunction "GND_3") (pintype "bidirectional"))
      (node (ref "Z2") (pin "1") (pintype "passive"))
      (node (ref "Z3") (pin "2") (pinfunction "A_2") (pintype "bidirectional"))
    )
    (net (code "40") (name "VCC") (class "Default")
      (node (ref "C10") (pin "2") (pinfunction "2_2") (pintype "passive"))
      (node (ref "C3") (pin "2") (pinfunction "2_2") (pintype "passive"))
      (node (ref "D2") (pin "1") (pinfunction "1_1") (pintype "bidirectional"))
      (node (ref "IC4") (pin "5") (pinfunction "VCC_5") (pintype "bidirectional"))
      (node (ref "J1") (pin "8") (pintype "passive"))
      (node (ref "L2") (pin "1") (pinfunction "1_1") (pintype "passive"))
      (node (ref "R7") (pin "1") (pinfunction "1_1") (pintype "passive"))
      (node (ref "Z2") (pin "2") (pintype "passive"))
    )
    (net (code "41") (name "VIN") (class "Default")
      (node (ref "D1") (pin "1") (pinfunction "K_1") (pintype "bidirectional"))
      (node (ref "J5") (pin "7") (pintype "passive"))
    )
    (net (code "42") (name "V_BATT") (class "Default")
      (node (ref "C11") (pin "2") (pinfunction "2_2") (pintype "passive"))
      (node (ref "C4") (pin "2") (pinfunction "2_2") (pintype "passive"))
      (node (ref "C9") (pin "2") (pinfunction "2_2") (pintype "passive"))
      (node (ref "IC1") (pin "4") (pinfunction "VOUT_4") (pintype "bidirectional"))
      (node (ref "IC3") (pin "5") (pinfunction "V+_5") (pintype "input"))
      (node (ref "K1") (pin "1") (pinfunction "+_1") (pintype "bidirectional"))
      (node (ref "K2") (pin "1") (pinfunction "+_1") (pintype "bidirectional"))
      (node (ref "R6") (pin "1") (pinfunction "1_1") (pintype "passive"))
      (node (ref "U1") (pin "5") (pinfunction "VCC_5") (pintype "bidirectional"))
      (node (ref "Z4") (pin "1") (pinfunction "K_1") (pintype "bidirectional"))
      (node (ref "Z5") (pin "1") (pinfunction "K_1") (pintype "bidirectional"))
    )
    (net (code "43") (name "unconnected-(IC1-NC_1-Pad3)") (class "Default")
      (node (ref "IC1") (pin "3") (pinfunction "NC_1_3") (pintype "bidirectional"))
    )
    (net (code "44") (name "unconnected-(IC1-NC_2-Pad5)") (class "Default")
      (node (ref "IC1") (pin "5") (pinfunction "NC_2_5") (pintype "bidirectional"))
    )
    (net (code "45") (name "unconnected-(IC4-N.C.-Pad1)") (class "Default")
      (node (ref "IC4") (pin "1") (pinfunction "N.C._1") (pintype "passive"))
    )
    (net (code "46") (name "unconnected-(J1-Pad4)") (class "Default")
      (node (ref "J1") (pin "4") (pintype "passive"))
    )
    (net (code "47") (name "unconnected-(J1-Pad5)") (class "Default")
      (node (ref "J1") (pin "5") (pintype "passive"))
    )
    (net (code "48") (name "unconnected-(J1-Pad6)") (class "Default")
      (node (ref "J1") (pin "6") (pintype "passive"))
    )
    (net (code "49") (name "unconnected-(J3-Pad1)") (class "Default")
      (node (ref "J3") (pin "1") (pintype "passive"))
    )
    (net (code "50") (name "unconnected-(J3-Pad2)") (class "Default")
      (node (ref "J3") (pin "2") (pintype "passive"))
    )
    (net (code "51") (name "unconnected-(J3-Pad3)") (class "Default")
      (node (ref "J3") (pin "3") (pintype "passive"))
    )
    (net (code "52") (name "unconnected-(J3-Pad4)") (class "Default")
      (node (ref "J3") (pin "4") (pintype "passive"))
    )
    (net (code "53") (name "unconnected-(J3-Pad5)") (class "Default")
      (node (ref "J3") (pin "5") (pintype "passive"))
    )
    (net (code "54") (name "unconnected-(J3-Pad6)") (class "Default")
      (node (ref "J3") (pin "6") (pintype "passive"))
    )
    (net (code "55") (name "unconnected-(J3-Pad7)") (class "Default")
      (node (ref "J3") (pin "7") (pintype "passive"))
    )
    (net (code "56") (name "unconnected-(J4-Pad1)") (class "Default")
      (node (ref "J4") (pin "1") (pintype "passive"))
    )
    (net (code "57") (name "unconnected-(J4-Pad2)") (class "Default")
      (node (ref "J4") (pin "2") (pintype "passive"))
    )
    (net (code "58") (name "unconnected-(J4-Pad3)") (class "Default")
      (node (ref "J4") (pin "3") (pintype "passive"))
    )
    (net (code "59") (name "unconnected-(J4-Pad4)") (class "Default")
      (node (ref "J4") (pin "4") (pintype "passive"))
    )
    (net (code "60") (name "unconnected-(J4-Pad5)") (class "Default")
      (node (ref "J4") (pin "5") (pintype "passive"))
    )
    (net (code "61") (name "unconnected-(J4-Pad6)") (class "Default")
      (node (ref "J4") (pin "6") (pintype "passive"))
    )
    (net (code "62") (name "unconnected-(J4-Pad7)") (class "Default")
      (node (ref "J4") (pin "7") (pintype "passive"))
    )
    (net (code "63") (name "unconnected-(J4-Pad8)") (class "Default")
      (node (ref "J4") (pin "8") (pintype "passive"))
    )
    (net (code "64") (name "unconnected-(J5-Pad1)") (class "Default")
      (node (ref "J5") (pin "1") (pintype "passive"))
    )
    (net (code "65") (name "unconnected-(J5-Pad2)") (class "Default")
      (node (ref "J5") (pin "2") (pintype "passive"))
    )
    (net (code "66") (name "unconnected-(J5-Pad4)") (class "Default")
      (node (ref "J5") (pin "4") (pintype "passive"))
    )
    (net (code "67") (name "unconnected-(J5-Pad5)") (class "Default")
      (node (ref "J5") (pin "5") (pintype "passive"))
    )
    (net (code "68") (name "unconnected-(J5-Pad6)") (class "Default")
      (node (ref "J5") (pin "6") (pintype "passive"))
    )
    (net (code "69") (name "unconnected-(U1-NC-Pad1)") (class "Default")
      (node (ref "U1") (pin "1") (pinfunction "NC_1") (pintype "passive"))
    )
  )
)
